# DIO_Isolation_Sheet.net
KiCad netlist of a schematic drawn in Altium Designer
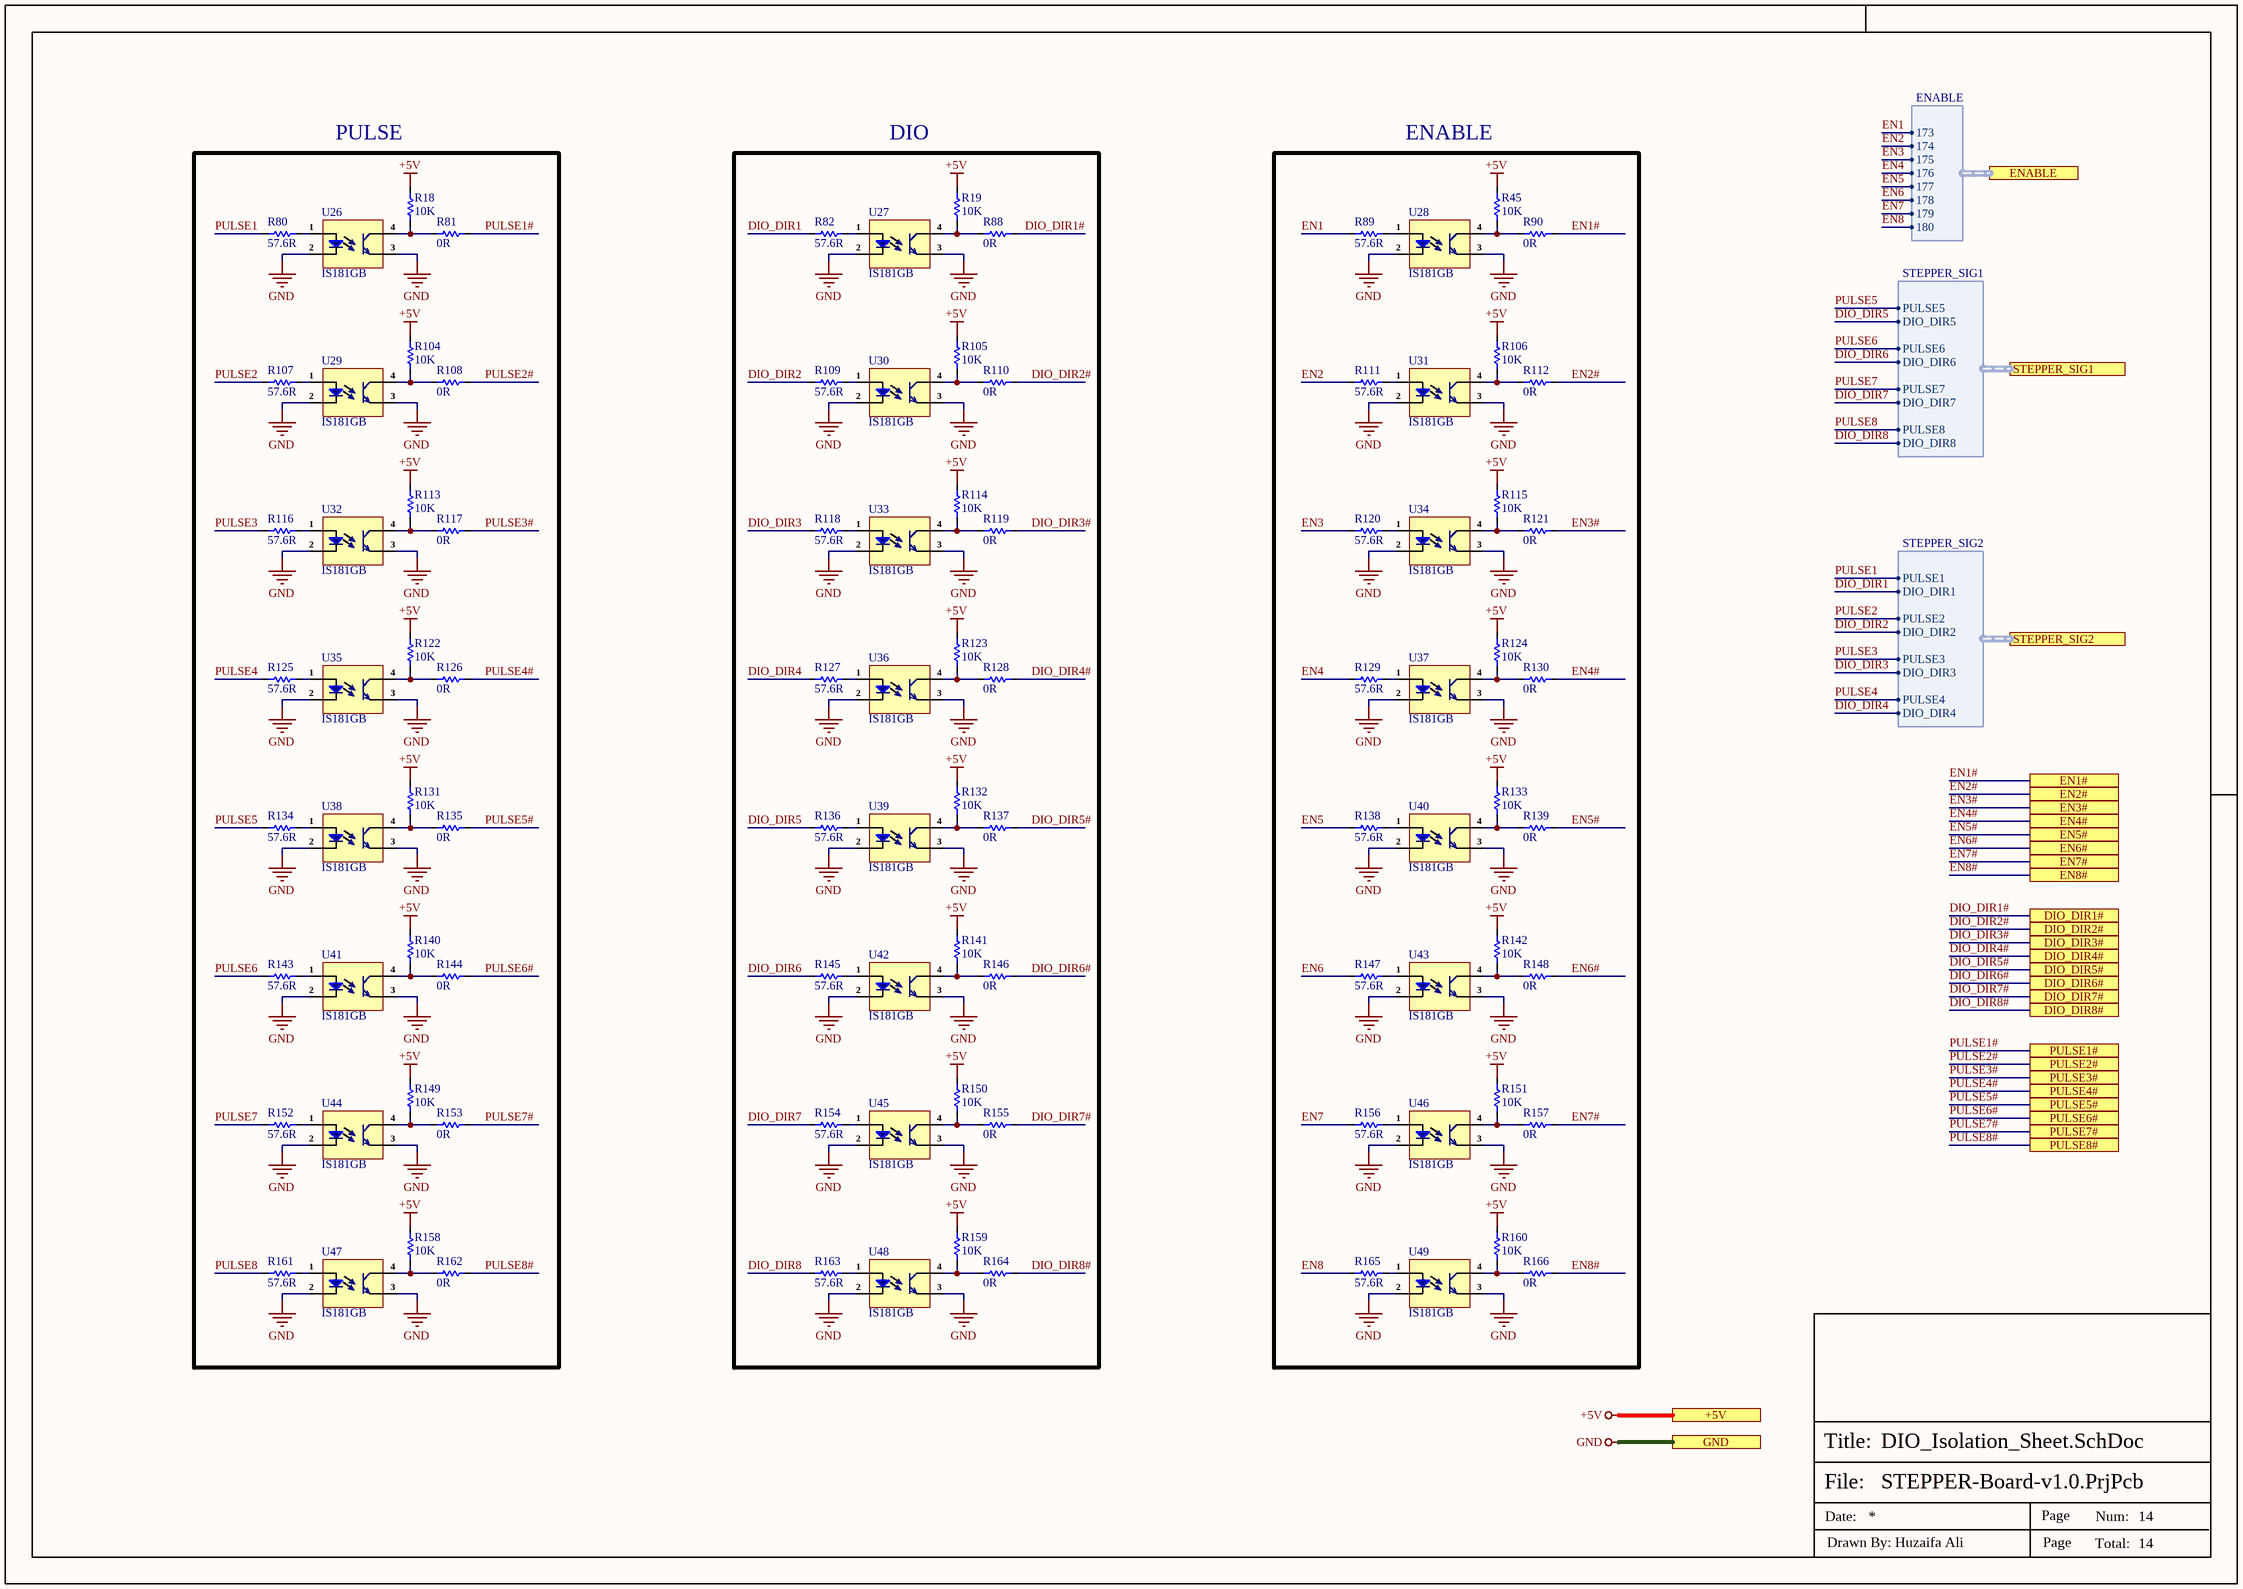
[diagram p0: DIO_Isolation_Sheet.SchDoc]

(export (version "E")
  (design (tool "Eeschema 10.0.6"))
  (components
    (comp (ref "R18")
      (value "10K")
      (footprint "Res-0402")
      (description "RES 10K OHM 1% 1/16W 0402")
      (fields
        (field (name "MANUFACTURER") "Yageo")
        (field (name "MANUFACTURER PART NUMBER") "RC0402FR-0710KL")
      )
      (libsource (lib "eSpark Libraries") (part "RC0402FR-0710KL"))
    )
    (comp (ref "R19")
      (value "10K")
      (footprint "Res-0402")
      (description "RES 10K OHM 1% 1/16W 0402")
      (fields
        (field (name "MANUFACTURER") "Yageo")
        (field (name "MANUFACTURER PART NUMBER") "RC0402FR-0710KL")
      )
      (libsource (lib "eSpark Libraries") (part "RC0402FR-0710KL"))
    )
    (comp (ref "R45")
      (value "10K")
      (footprint "Res-0402")
      (description "RES 10K OHM 1% 1/16W 0402")
      (fields
        (field (name "MANUFACTURER") "Yageo")
        (field (name "MANUFACTURER PART NUMBER") "RC0402FR-0710KL")
      )
      (libsource (lib "eSpark Libraries") (part "RC0402FR-0710KL"))
    )
    (comp (ref "R80")
      (value "57.6R")
      (footprint "Res-0402")
      (description "RES SMD 57.6 OHM 1% 1/10W 0402")
      (fields
        (field (name "MANUFACTURER") "Panasonic")
        (field (name "MANUFACTURER PART NUMBER") "ERJ-2RKF57R6X")
      )
      (libsource (lib "eSpark Libraries") (part "ERJ-2RKF57R6X"))
    )
    (comp (ref "R81")
      (value "0R")
      (footprint "Res-0402")
      (description "RES 0 OHM JUMPER 1/16W 0402")
      (fields
        (field (name "MANUFACTURER") "Yageo")
        (field (name "MANUFACTURER PART NUMBER") "RC0402FR-070RL")
      )
      (libsource (lib "eSpark Libraries") (part "RC0402FR-070RL"))
    )
    (comp (ref "R82")
      (value "57.6R")
      (footprint "Res-0402")
      (description "RES SMD 57.6 OHM 1% 1/10W 0402")
      (fields
        (field (name "MANUFACTURER") "Panasonic")
        (field (name "MANUFACTURER PART NUMBER") "ERJ-2RKF57R6X")
      )
      (libsource (lib "eSpark Libraries") (part "ERJ-2RKF57R6X"))
    )
    (comp (ref "R88")
      (value "0R")
      (footprint "Res-0402")
      (description "RES 0 OHM JUMPER 1/16W 0402")
      (fields
        (field (name "MANUFACTURER") "Yageo")
        (field (name "MANUFACTURER PART NUMBER") "RC0402FR-070RL")
      )
      (libsource (lib "eSpark Libraries") (part "RC0402FR-070RL"))
    )
    (comp (ref "R89")
      (value "57.6R")
      (footprint "Res-0402")
      (description "RES SMD 57.6 OHM 1% 1/10W 0402")
      (fields
        (field (name "MANUFACTURER") "Panasonic")
        (field (name "MANUFACTURER PART NUMBER") "ERJ-2RKF57R6X")
      )
      (libsource (lib "eSpark Libraries") (part "ERJ-2RKF57R6X"))
    )
    (comp (ref "R90")
      (value "0R")
      (footprint "Res-0402")
      (description "RES 0 OHM JUMPER 1/16W 0402")
      (fields
        (field (name "MANUFACTURER") "Yageo")
        (field (name "MANUFACTURER PART NUMBER") "RC0402FR-070RL")
      )
      (libsource (lib "eSpark Libraries") (part "RC0402FR-070RL"))
    )
    (comp (ref "R104")
      (value "10K")
      (footprint "Res-0402")
      (description "RES 10K OHM 1% 1/16W 0402")
      (fields
        (field (name "MANUFACTURER") "Yageo")
        (field (name "MANUFACTURER PART NUMBER") "RC0402FR-0710KL")
      )
      (libsource (lib "eSpark Libraries") (part "RC0402FR-0710KL"))
    )
    (comp (ref "R105")
      (value "10K")
      (footprint "Res-0402")
      (description "RES 10K OHM 1% 1/16W 0402")
      (fields
        (field (name "MANUFACTURER") "Yageo")
        (field (name "MANUFACTURER PART NUMBER") "RC0402FR-0710KL")
      )
      (libsource (lib "eSpark Libraries") (part "RC0402FR-0710KL"))
    )
    (comp (ref "R106")
      (value "10K")
      (footprint "Res-0402")
      (description "RES 10K OHM 1% 1/16W 0402")
      (fields
        (field (name "MANUFACTURER") "Yageo")
        (field (name "MANUFACTURER PART NUMBER") "RC0402FR-0710KL")
      )
      (libsource (lib "eSpark Libraries") (part "RC0402FR-0710KL"))
    )
    (comp (ref "R107")
      (value "57.6R")
      (footprint "Res-0402")
      (description "RES SMD 57.6 OHM 1% 1/10W 0402")
      (fields
        (field (name "MANUFACTURER") "Panasonic")
        (field (name "MANUFACTURER PART NUMBER") "ERJ-2RKF57R6X")
      )
      (libsource (lib "eSpark Libraries") (part "ERJ-2RKF57R6X"))
    )
    (comp (ref "R108")
      (value "0R")
      (footprint "Res-0402")
      (description "RES 0 OHM JUMPER 1/16W 0402")
      (fields
        (field (name "MANUFACTURER") "Yageo")
        (field (name "MANUFACTURER PART NUMBER") "RC0402FR-070RL")
      )
      (libsource (lib "eSpark Libraries") (part "RC0402FR-070RL"))
    )
    (comp (ref "R109")
      (value "57.6R")
      (footprint "Res-0402")
      (description "RES SMD 57.6 OHM 1% 1/10W 0402")
      (fields
        (field (name "MANUFACTURER") "Panasonic")
        (field (name "MANUFACTURER PART NUMBER") "ERJ-2RKF57R6X")
      )
      (libsource (lib "eSpark Libraries") (part "ERJ-2RKF57R6X"))
    )
    (comp (ref "R110")
      (value "0R")
      (footprint "Res-0402")
      (description "RES 0 OHM JUMPER 1/16W 0402")
      (fields
        (field (name "MANUFACTURER") "Yageo")
        (field (name "MANUFACTURER PART NUMBER") "RC0402FR-070RL")
      )
      (libsource (lib "eSpark Libraries") (part "RC0402FR-070RL"))
    )
    (comp (ref "R111")
      (value "57.6R")
      (footprint "Res-0402")
      (description "RES SMD 57.6 OHM 1% 1/10W 0402")
      (fields
        (field (name "MANUFACTURER") "Panasonic")
        (field (name "MANUFACTURER PART NUMBER") "ERJ-2RKF57R6X")
      )
      (libsource (lib "eSpark Libraries") (part "ERJ-2RKF57R6X"))
    )
    (comp (ref "R112")
      (value "0R")
      (footprint "Res-0402")
      (description "RES 0 OHM JUMPER 1/16W 0402")
      (fields
        (field (name "MANUFACTURER") "Yageo")
        (field (name "MANUFACTURER PART NUMBER") "RC0402FR-070RL")
      )
      (libsource (lib "eSpark Libraries") (part "RC0402FR-070RL"))
    )
    (comp (ref "R113")
      (value "10K")
      (footprint "Res-0402")
      (description "RES 10K OHM 1% 1/16W 0402")
      (fields
        (field (name "MANUFACTURER") "Yageo")
        (field (name "MANUFACTURER PART NUMBER") "RC0402FR-0710KL")
      )
      (libsource (lib "eSpark Libraries") (part "RC0402FR-0710KL"))
    )
    (comp (ref "R114")
      (value "10K")
      (footprint "Res-0402")
      (description "RES 10K OHM 1% 1/16W 0402")
      (fields
        (field (name "MANUFACTURER") "Yageo")
        (field (name "MANUFACTURER PART NUMBER") "RC0402FR-0710KL")
      )
      (libsource (lib "eSpark Libraries") (part "RC0402FR-0710KL"))
    )
    (comp (ref "R115")
      (value "10K")
      (footprint "Res-0402")
      (description "RES 10K OHM 1% 1/16W 0402")
      (fields
        (field (name "MANUFACTURER") "Yageo")
        (field (name "MANUFACTURER PART NUMBER") "RC0402FR-0710KL")
      )
      (libsource (lib "eSpark Libraries") (part "RC0402FR-0710KL"))
    )
    (comp (ref "R116")
      (value "57.6R")
      (footprint "Res-0402")
      (description "RES SMD 57.6 OHM 1% 1/10W 0402")
      (fields
        (field (name "MANUFACTURER") "Panasonic")
        (field (name "MANUFACTURER PART NUMBER") "ERJ-2RKF57R6X")
      )
      (libsource (lib "eSpark Libraries") (part "ERJ-2RKF57R6X"))
    )
    (comp (ref "R117")
      (value "0R")
      (footprint "Res-0402")
      (description "RES 0 OHM JUMPER 1/16W 0402")
      (fields
        (field (name "MANUFACTURER") "Yageo")
        (field (name "MANUFACTURER PART NUMBER") "RC0402FR-070RL")
      )
      (libsource (lib "eSpark Libraries") (part "RC0402FR-070RL"))
    )
    (comp (ref "R118")
      (value "57.6R")
      (footprint "Res-0402")
      (description "RES SMD 57.6 OHM 1% 1/10W 0402")
      (fields
        (field (name "MANUFACTURER") "Panasonic")
        (field (name "MANUFACTURER PART NUMBER") "ERJ-2RKF57R6X")
      )
      (libsource (lib "eSpark Libraries") (part "ERJ-2RKF57R6X"))
    )
    (comp (ref "R119")
      (value "0R")
      (footprint "Res-0402")
      (description "RES 0 OHM JUMPER 1/16W 0402")
      (fields
        (field (name "MANUFACTURER") "Yageo")
        (field (name "MANUFACTURER PART NUMBER") "RC0402FR-070RL")
      )
      (libsource (lib "eSpark Libraries") (part "RC0402FR-070RL"))
    )
    (comp (ref "R120")
      (value "57.6R")
      (footprint "Res-0402")
      (description "RES SMD 57.6 OHM 1% 1/10W 0402")
      (fields
        (field (name "MANUFACTURER") "Panasonic")
        (field (name "MANUFACTURER PART NUMBER") "ERJ-2RKF57R6X")
      )
      (libsource (lib "eSpark Libraries") (part "ERJ-2RKF57R6X"))
    )
    (comp (ref "R121")
      (value "0R")
      (footprint "Res-0402")
      (description "RES 0 OHM JUMPER 1/16W 0402")
      (fields
        (field (name "MANUFACTURER") "Yageo")
        (field (name "MANUFACTURER PART NUMBER") "RC0402FR-070RL")
      )
      (libsource (lib "eSpark Libraries") (part "RC0402FR-070RL"))
    )
    (comp (ref "R122")
      (value "10K")
      (footprint "Res-0402")
      (description "RES 10K OHM 1% 1/16W 0402")
      (fields
        (field (name "MANUFACTURER") "Yageo")
        (field (name "MANUFACTURER PART NUMBER") "RC0402FR-0710KL")
      )
      (libsource (lib "eSpark Libraries") (part "RC0402FR-0710KL"))
    )
    (comp (ref "R123")
      (value "10K")
      (footprint "Res-0402")
      (description "RES 10K OHM 1% 1/16W 0402")
      (fields
        (field (name "MANUFACTURER") "Yageo")
        (field (name "MANUFACTURER PART NUMBER") "RC0402FR-0710KL")
      )
      (libsource (lib "eSpark Libraries") (part "RC0402FR-0710KL"))
    )
    (comp (ref "R124")
      (value "10K")
      (footprint "Res-0402")
      (description "RES 10K OHM 1% 1/16W 0402")
      (fields
        (field (name "MANUFACTURER") "Yageo")
        (field (name "MANUFACTURER PART NUMBER") "RC0402FR-0710KL")
      )
      (libsource (lib "eSpark Libraries") (part "RC0402FR-0710KL"))
    )
    (comp (ref "R125")
      (value "57.6R")
      (footprint "Res-0402")
      (description "RES SMD 57.6 OHM 1% 1/10W 0402")
      (fields
        (field (name "MANUFACTURER") "Panasonic")
        (field (name "MANUFACTURER PART NUMBER") "ERJ-2RKF57R6X")
      )
      (libsource (lib "eSpark Libraries") (part "ERJ-2RKF57R6X"))
    )
    (comp (ref "R126")
      (value "0R")
      (footprint "Res-0402")
      (description "RES 0 OHM JUMPER 1/16W 0402")
      (fields
        (field (name "MANUFACTURER") "Yageo")
        (field (name "MANUFACTURER PART NUMBER") "RC0402FR-070RL")
      )
      (libsource (lib "eSpark Libraries") (part "RC0402FR-070RL"))
    )
    (comp (ref "R127")
      (value "57.6R")
      (footprint "Res-0402")
      (description "RES SMD 57.6 OHM 1% 1/10W 0402")
      (fields
        (field (name "MANUFACTURER") "Panasonic")
        (field (name "MANUFACTURER PART NUMBER") "ERJ-2RKF57R6X")
      )
      (libsource (lib "eSpark Libraries") (part "ERJ-2RKF57R6X"))
    )
    (comp (ref "R128")
      (value "0R")
      (footprint "Res-0402")
      (description "RES 0 OHM JUMPER 1/16W 0402")
      (fields
        (field (name "MANUFACTURER") "Yageo")
        (field (name "MANUFACTURER PART NUMBER") "RC0402FR-070RL")
      )
      (libsource (lib "eSpark Libraries") (part "RC0402FR-070RL"))
    )
    (comp (ref "R129")
      (value "57.6R")
      (footprint "Res-0402")
      (description "RES SMD 57.6 OHM 1% 1/10W 0402")
      (fields
        (field (name "MANUFACTURER") "Panasonic")
        (field (name "MANUFACTURER PART NUMBER") "ERJ-2RKF57R6X")
      )
      (libsource (lib "eSpark Libraries") (part "ERJ-2RKF57R6X"))
    )
    (comp (ref "R130")
      (value "0R")
      (footprint "Res-0402")
      (description "RES 0 OHM JUMPER 1/16W 0402")
      (fields
        (field (name "MANUFACTURER") "Yageo")
        (field (name "MANUFACTURER PART NUMBER") "RC0402FR-070RL")
      )
      (libsource (lib "eSpark Libraries") (part "RC0402FR-070RL"))
    )
    (comp (ref "R131")
      (value "10K")
      (footprint "Res-0402")
      (description "RES 10K OHM 1% 1/16W 0402")
      (fields
        (field (name "MANUFACTURER") "Yageo")
        (field (name "MANUFACTURER PART NUMBER") "RC0402FR-0710KL")
      )
      (libsource (lib "eSpark Libraries") (part "RC0402FR-0710KL"))
    )
    (comp (ref "R132")
      (value "10K")
      (footprint "Res-0402")
      (description "RES 10K OHM 1% 1/16W 0402")
      (fields
        (field (name "MANUFACTURER") "Yageo")
        (field (name "MANUFACTURER PART NUMBER") "RC0402FR-0710KL")
      )
      (libsource (lib "eSpark Libraries") (part "RC0402FR-0710KL"))
    )
    (comp (ref "R133")
      (value "10K")
      (footprint "Res-0402")
      (description "RES 10K OHM 1% 1/16W 0402")
      (fields
        (field (name "MANUFACTURER") "Yageo")
        (field (name "MANUFACTURER PART NUMBER") "RC0402FR-0710KL")
      )
      (libsource (lib "eSpark Libraries") (part "RC0402FR-0710KL"))
    )
    (comp (ref "R134")
      (value "57.6R")
      (footprint "Res-0402")
      (description "RES SMD 57.6 OHM 1% 1/10W 0402")
      (fields
        (field (name "MANUFACTURER") "Panasonic")
        (field (name "MANUFACTURER PART NUMBER") "ERJ-2RKF57R6X")
      )
      (libsource (lib "eSpark Libraries") (part "ERJ-2RKF57R6X"))
    )
    (comp (ref "R135")
      (value "0R")
      (footprint "Res-0402")
      (description "RES 0 OHM JUMPER 1/16W 0402")
      (fields
        (field (name "MANUFACTURER") "Yageo")
        (field (name "MANUFACTURER PART NUMBER") "RC0402FR-070RL")
      )
      (libsource (lib "eSpark Libraries") (part "RC0402FR-070RL"))
    )
    (comp (ref "R136")
      (value "57.6R")
      (footprint "Res-0402")
      (description "RES SMD 57.6 OHM 1% 1/10W 0402")
      (fields
        (field (name "MANUFACTURER") "Panasonic")
        (field (name "MANUFACTURER PART NUMBER") "ERJ-2RKF57R6X")
      )
      (libsource (lib "eSpark Libraries") (part "ERJ-2RKF57R6X"))
    )
    (comp (ref "R137")
      (value "0R")
      (footprint "Res-0402")
      (description "RES 0 OHM JUMPER 1/16W 0402")
      (fields
        (field (name "MANUFACTURER") "Yageo")
        (field (name "MANUFACTURER PART NUMBER") "RC0402FR-070RL")
      )
      (libsource (lib "eSpark Libraries") (part "RC0402FR-070RL"))
    )
    (comp (ref "R138")
      (value "57.6R")
      (footprint "Res-0402")
      (description "RES SMD 57.6 OHM 1% 1/10W 0402")
      (fields
        (field (name "MANUFACTURER") "Panasonic")
        (field (name "MANUFACTURER PART NUMBER") "ERJ-2RKF57R6X")
      )
      (libsource (lib "eSpark Libraries") (part "ERJ-2RKF57R6X"))
    )
    (comp (ref "R139")
      (value "0R")
      (footprint "Res-0402")
      (description "RES 0 OHM JUMPER 1/16W 0402")
      (fields
        (field (name "MANUFACTURER") "Yageo")
        (field (name "MANUFACTURER PART NUMBER") "RC0402FR-070RL")
      )
      (libsource (lib "eSpark Libraries") (part "RC0402FR-070RL"))
    )
    (comp (ref "R140")
      (value "10K")
      (footprint "Res-0402")
      (description "RES 10K OHM 1% 1/16W 0402")
      (fields
        (field (name "MANUFACTURER") "Yageo")
        (field (name "MANUFACTURER PART NUMBER") "RC0402FR-0710KL")
      )
      (libsource (lib "eSpark Libraries") (part "RC0402FR-0710KL"))
    )
    (comp (ref "R141")
      (value "10K")
      (footprint "Res-0402")
      (description "RES 10K OHM 1% 1/16W 0402")
      (fields
        (field (name "MANUFACTURER") "Yageo")
        (field (name "MANUFACTURER PART NUMBER") "RC0402FR-0710KL")
      )
      (libsource (lib "eSpark Libraries") (part "RC0402FR-0710KL"))
    )
    (comp (ref "R142")
      (value "10K")
      (footprint "Res-0402")
      (description "RES 10K OHM 1% 1/16W 0402")
      (fields
        (field (name "MANUFACTURER") "Yageo")
        (field (name "MANUFACTURER PART NUMBER") "RC0402FR-0710KL")
      )
      (libsource (lib "eSpark Libraries") (part "RC0402FR-0710KL"))
    )
    (comp (ref "R143")
      (value "57.6R")
      (footprint "Res-0402")
      (description "RES SMD 57.6 OHM 1% 1/10W 0402")
      (fields
        (field (name "MANUFACTURER") "Panasonic")
        (field (name "MANUFACTURER PART NUMBER") "ERJ-2RKF57R6X")
      )
      (libsource (lib "eSpark Libraries") (part "ERJ-2RKF57R6X"))
    )
    (comp (ref "R144")
      (value "0R")
      (footprint "Res-0402")
      (description "RES 0 OHM JUMPER 1/16W 0402")
      (fields
        (field (name "MANUFACTURER") "Yageo")
        (field (name "MANUFACTURER PART NUMBER") "RC0402FR-070RL")
      )
      (libsource (lib "eSpark Libraries") (part "RC0402FR-070RL"))
    )
    (comp (ref "R145")
      (value "57.6R")
      (footprint "Res-0402")
      (description "RES SMD 57.6 OHM 1% 1/10W 0402")
      (fields
        (field (name "MANUFACTURER") "Panasonic")
        (field (name "MANUFACTURER PART NUMBER") "ERJ-2RKF57R6X")
      )
      (libsource (lib "eSpark Libraries") (part "ERJ-2RKF57R6X"))
    )
    (comp (ref "R146")
      (value "0R")
      (footprint "Res-0402")
      (description "RES 0 OHM JUMPER 1/16W 0402")
      (fields
        (field (name "MANUFACTURER") "Yageo")
        (field (name "MANUFACTURER PART NUMBER") "RC0402FR-070RL")
      )
      (libsource (lib "eSpark Libraries") (part "RC0402FR-070RL"))
    )
    (comp (ref "R147")
      (value "57.6R")
      (footprint "Res-0402")
      (description "RES SMD 57.6 OHM 1% 1/10W 0402")
      (fields
        (field (name "MANUFACTURER") "Panasonic")
        (field (name "MANUFACTURER PART NUMBER") "ERJ-2RKF57R6X")
      )
      (libsource (lib "eSpark Libraries") (part "ERJ-2RKF57R6X"))
    )
    (comp (ref "R148")
      (value "0R")
      (footprint "Res-0402")
      (description "RES 0 OHM JUMPER 1/16W 0402")
      (fields
        (field (name "MANUFACTURER") "Yageo")
        (field (name "MANUFACTURER PART NUMBER") "RC0402FR-070RL")
      )
      (libsource (lib "eSpark Libraries") (part "RC0402FR-070RL"))
    )
    (comp (ref "R149")
      (value "10K")
      (footprint "Res-0402")
      (description "RES 10K OHM 1% 1/16W 0402")
      (fields
        (field (name "MANUFACTURER") "Yageo")
        (field (name "MANUFACTURER PART NUMBER") "RC0402FR-0710KL")
      )
      (libsource (lib "eSpark Libraries") (part "RC0402FR-0710KL"))
    )
    (comp (ref "R150")
      (value "10K")
      (footprint "Res-0402")
      (description "RES 10K OHM 1% 1/16W 0402")
      (fields
        (field (name "MANUFACTURER") "Yageo")
        (field (name "MANUFACTURER PART NUMBER") "RC0402FR-0710KL")
      )
      (libsource (lib "eSpark Libraries") (part "RC0402FR-0710KL"))
    )
    (comp (ref "R151")
      (value "10K")
      (footprint "Res-0402")
      (description "RES 10K OHM 1% 1/16W 0402")
      (fields
        (field (name "MANUFACTURER") "Yageo")
        (field (name "MANUFACTURER PART NUMBER") "RC0402FR-0710KL")
      )
      (libsource (lib "eSpark Libraries") (part "RC0402FR-0710KL"))
    )
    (comp (ref "R152")
      (value "57.6R")
      (footprint "Res-0402")
      (description "RES SMD 57.6 OHM 1% 1/10W 0402")
      (fields
        (field (name "MANUFACTURER") "Panasonic")
        (field (name "MANUFACTURER PART NUMBER") "ERJ-2RKF57R6X")
      )
      (libsource (lib "eSpark Libraries") (part "ERJ-2RKF57R6X"))
    )
    (comp (ref "R153")
      (value "0R")
      (footprint "Res-0402")
      (description "RES 0 OHM JUMPER 1/16W 0402")
      (fields
        (field (name "MANUFACTURER") "Yageo")
        (field (name "MANUFACTURER PART NUMBER") "RC0402FR-070RL")
      )
      (libsource (lib "eSpark Libraries") (part "RC0402FR-070RL"))
    )
    (comp (ref "R154")
      (value "57.6R")
      (footprint "Res-0402")
      (description "RES SMD 57.6 OHM 1% 1/10W 0402")
      (fields
        (field (name "MANUFACTURER") "Panasonic")
        (field (name "MANUFACTURER PART NUMBER") "ERJ-2RKF57R6X")
      )
      (libsource (lib "eSpark Libraries") (part "ERJ-2RKF57R6X"))
    )
    (comp (ref "R155")
      (value "0R")
      (footprint "Res-0402")
      (description "RES 0 OHM JUMPER 1/16W 0402")
      (fields
        (field (name "MANUFACTURER") "Yageo")
        (field (name "MANUFACTURER PART NUMBER") "RC0402FR-070RL")
      )
      (libsource (lib "eSpark Libraries") (part "RC0402FR-070RL"))
    )
    (comp (ref "R156")
      (value "57.6R")
      (footprint "Res-0402")
      (description "RES SMD 57.6 OHM 1% 1/10W 0402")
      (fields
        (field (name "MANUFACTURER") "Panasonic")
        (field (name "MANUFACTURER PART NUMBER") "ERJ-2RKF57R6X")
      )
      (libsource (lib "eSpark Libraries") (part "ERJ-2RKF57R6X"))
    )
    (comp (ref "R157")
      (value "0R")
      (footprint "Res-0402")
      (description "RES 0 OHM JUMPER 1/16W 0402")
      (fields
        (field (name "MANUFACTURER") "Yageo")
        (field (name "MANUFACTURER PART NUMBER") "RC0402FR-070RL")
      )
      (libsource (lib "eSpark Libraries") (part "RC0402FR-070RL"))
    )
    (comp (ref "R158")
      (value "10K")
      (footprint "Res-0402")
      (description "RES 10K OHM 1% 1/16W 0402")
      (fields
        (field (name "MANUFACTURER") "Yageo")
        (field (name "MANUFACTURER PART NUMBER") "RC0402FR-0710KL")
      )
      (libsource (lib "eSpark Libraries") (part "RC0402FR-0710KL"))
    )
    (comp (ref "R159")
      (value "10K")
      (footprint "Res-0402")
      (description "RES 10K OHM 1% 1/16W 0402")
      (fields
        (field (name "MANUFACTURER") "Yageo")
        (field (name "MANUFACTURER PART NUMBER") "RC0402FR-0710KL")
      )
      (libsource (lib "eSpark Libraries") (part "RC0402FR-0710KL"))
    )
    (comp (ref "R160")
      (value "10K")
      (footprint "Res-0402")
      (description "RES 10K OHM 1% 1/16W 0402")
      (fields
        (field (name "MANUFACTURER") "Yageo")
        (field (name "MANUFACTURER PART NUMBER") "RC0402FR-0710KL")
      )
      (libsource (lib "eSpark Libraries") (part "RC0402FR-0710KL"))
    )
    (comp (ref "R161")
      (value "57.6R")
      (footprint "Res-0402")
      (description "RES SMD 57.6 OHM 1% 1/10W 0402")
      (fields
        (field (name "MANUFACTURER") "Panasonic")
        (field (name "MANUFACTURER PART NUMBER") "ERJ-2RKF57R6X")
      )
      (libsource (lib "eSpark Libraries") (part "ERJ-2RKF57R6X"))
    )
    (comp (ref "R162")
      (value "0R")
      (footprint "Res-0402")
      (description "RES 0 OHM JUMPER 1/16W 0402")
      (fields
        (field (name "MANUFACTURER") "Yageo")
        (field (name "MANUFACTURER PART NUMBER") "RC0402FR-070RL")
      )
      (libsource (lib "eSpark Libraries") (part "RC0402FR-070RL"))
    )
    (comp (ref "R163")
      (value "57.6R")
      (footprint "Res-0402")
      (description "RES SMD 57.6 OHM 1% 1/10W 0402")
      (fields
        (field (name "MANUFACTURER") "Panasonic")
        (field (name "MANUFACTURER PART NUMBER") "ERJ-2RKF57R6X")
      )
      (libsource (lib "eSpark Libraries") (part "ERJ-2RKF57R6X"))
    )
    (comp (ref "R164")
      (value "0R")
      (footprint "Res-0402")
      (description "RES 0 OHM JUMPER 1/16W 0402")
      (fields
        (field (name "MANUFACTURER") "Yageo")
        (field (name "MANUFACTURER PART NUMBER") "RC0402FR-070RL")
      )
      (libsource (lib "eSpark Libraries") (part "RC0402FR-070RL"))
    )
    (comp (ref "R165")
      (value "57.6R")
      (footprint "Res-0402")
      (description "RES SMD 57.6 OHM 1% 1/10W 0402")
      (fields
        (field (name "MANUFACTURER") "Panasonic")
        (field (name "MANUFACTURER PART NUMBER") "ERJ-2RKF57R6X")
      )
      (libsource (lib "eSpark Libraries") (part "ERJ-2RKF57R6X"))
    )
    (comp (ref "R166")
      (value "0R")
      (footprint "Res-0402")
      (description "RES 0 OHM JUMPER 1/16W 0402")
      (fields
        (field (name "MANUFACTURER") "Yageo")
        (field (name "MANUFACTURER PART NUMBER") "RC0402FR-070RL")
      )
      (libsource (lib "eSpark Libraries") (part "RC0402FR-070RL"))
    )
    (comp (ref "U26")
      (value "IS181GB")
      (footprint "SOP-4_2.54")
      (description "Optoisolator Transistor Output 3750Vrms 1 Channel")
      (fields (field (name "MANUFACTURER") "Isocom") (field (name "LCSC PART NUMBER") "C84196"))
      (libsource (lib "eSpark Libraries") (part "IS181GB"))
    )
    (comp (ref "U27")
      (value "IS181GB")
      (footprint "SOP-4_2.54")
      (description "Optoisolator Transistor Output 3750Vrms 1 Channel")
      (fields (field (name "MANUFACTURER") "Isocom") (field (name "LCSC PART NUMBER") "C84196"))
      (libsource (lib "eSpark Libraries") (part "IS181GB"))
    )
    (comp (ref "U28")
      (value "IS181GB")
      (footprint "SOP-4_2.54")
      (description "Optoisolator Transistor Output 3750Vrms 1 Channel")
      (fields (field (name "MANUFACTURER") "Isocom") (field (name "LCSC PART NUMBER") "C84196"))
      (libsource (lib "eSpark Libraries") (part "IS181GB"))
    )
    (comp (ref "U29")
      (value "IS181GB")
      (footprint "SOP-4_2.54")
      (description "Optoisolator Transistor Output 3750Vrms 1 Channel")
      (fields (field (name "MANUFACTURER") "Isocom") (field (name "LCSC PART NUMBER") "C84196"))
      (libsource (lib "eSpark Libraries") (part "IS181GB"))
    )
    (comp (ref "U30")
      (value "IS181GB")
      (footprint "SOP-4_2.54")
      (description "Optoisolator Transistor Output 3750Vrms 1 Channel")
      (fields (field (name "MANUFACTURER") "Isocom") (field (name "LCSC PART NUMBER") "C84196"))
      (libsource (lib "eSpark Libraries") (part "IS181GB"))
    )
    (comp (ref "U31")
      (value "IS181GB")
      (footprint "SOP-4_2.54")
      (description "Optoisolator Transistor Output 3750Vrms 1 Channel")
      (fields (field (name "MANUFACTURER") "Isocom") (field (name "LCSC PART NUMBER") "C84196"))
      (libsource (lib "eSpark Libraries") (part "IS181GB"))
    )
    (comp (ref "U32")
      (value "IS181GB")
      (footprint "SOP-4_2.54")
      (description "Optoisolator Transistor Output 3750Vrms 1 Channel")
      (fields (field (name "MANUFACTURER") "Isocom") (field (name "LCSC PART NUMBER") "C84196"))
      (libsource (lib "eSpark Libraries") (part "IS181GB"))
    )
    (comp (ref "U33")
      (value "IS181GB")
      (footprint "SOP-4_2.54")
      (description "Optoisolator Transistor Output 3750Vrms 1 Channel")
      (fields (field (name "MANUFACTURER") "Isocom") (field (name "LCSC PART NUMBER") "C84196"))
      (libsource (lib "eSpark Libraries") (part "IS181GB"))
    )
    (comp (ref "U34")
      (value "IS181GB")
      (footprint "SOP-4_2.54")
      (description "Optoisolator Transistor Output 3750Vrms 1 Channel")
      (fields (field (name "MANUFACTURER") "Isocom") (field (name "LCSC PART NUMBER") "C84196"))
      (libsource (lib "eSpark Libraries") (part "IS181GB"))
    )
    (comp (ref "U35")
      (value "IS181GB")
      (footprint "SOP-4_2.54")
      (description "Optoisolator Transistor Output 3750Vrms 1 Channel")
      (fields (field (name "MANUFACTURER") "Isocom") (field (name "LCSC PART NUMBER") "C84196"))
      (libsource (lib "eSpark Libraries") (part "IS181GB"))
    )
    (comp (ref "U36")
      (value "IS181GB")
      (footprint "SOP-4_2.54")
      (description "Optoisolator Transistor Output 3750Vrms 1 Channel")
      (fields (field (name "MANUFACTURER") "Isocom") (field (name "LCSC PART NUMBER") "C84196"))
      (libsource (lib "eSpark Libraries") (part "IS181GB"))
    )
    (comp (ref "U37")
      (value "IS181GB")
      (footprint "SOP-4_2.54")
      (description "Optoisolator Transistor Output 3750Vrms 1 Channel")
      (fields (field (name "MANUFACTURER") "Isocom") (field (name "LCSC PART NUMBER") "C84196"))
      (libsource (lib "eSpark Libraries") (part "IS181GB"))
    )
    (comp (ref "U38")
      (value "IS181GB")
      (footprint "SOP-4_2.54")
      (description "Optoisolator Transistor Output 3750Vrms 1 Channel")
      (fields (field (name "MANUFACTURER") "Isocom") (field (name "LCSC PART NUMBER") "C84196"))
      (libsource (lib "eSpark Libraries") (part "IS181GB"))
    )
    (comp (ref "U39")
      (value "IS181GB")
      (footprint "SOP-4_2.54")
      (description "Optoisolator Transistor Output 3750Vrms 1 Channel")
      (fields (field (name "MANUFACTURER") "Isocom") (field (name "LCSC PART NUMBER") "C84196"))
      (libsource (lib "eSpark Libraries") (part "IS181GB"))
    )
    (comp (ref "U40")
      (value "IS181GB")
      (footprint "SOP-4_2.54")
      (description "Optoisolator Transistor Output 3750Vrms 1 Channel")
      (fields (field (name "MANUFACTURER") "Isocom") (field (name "LCSC PART NUMBER") "C84196"))
      (libsource (lib "eSpark Libraries") (part "IS181GB"))
    )
    (comp (ref "U41")
      (value "IS181GB")
      (footprint "SOP-4_2.54")
      (description "Optoisolator Transistor Output 3750Vrms 1 Channel")
      (fields (field (name "MANUFACTURER") "Isocom") (field (name "LCSC PART NUMBER") "C84196"))
      (libsource (lib "eSpark Libraries") (part "IS181GB"))
    )
    (comp (ref "U42")
      (value "IS181GB")
      (footprint "SOP-4_2.54")
      (description "Optoisolator Transistor Output 3750Vrms 1 Channel")
      (fields (field (name "MANUFACTURER") "Isocom") (field (name "LCSC PART NUMBER") "C84196"))
      (libsource (lib "eSpark Libraries") (part "IS181GB"))
    )
    (comp (ref "U43")
      (value "IS181GB")
      (footprint "SOP-4_2.54")
      (description "Optoisolator Transistor Output 3750Vrms 1 Channel")
      (fields (field (name "MANUFACTURER") "Isocom") (field (name "LCSC PART NUMBER") "C84196"))
      (libsource (lib "eSpark Libraries") (part "IS181GB"))
    )
    (comp (ref "U44")
      (value "IS181GB")
      (footprint "SOP-4_2.54")
      (description "Optoisolator Transistor Output 3750Vrms 1 Channel")
      (fields (field (name "MANUFACTURER") "Isocom") (field (name "LCSC PART NUMBER") "C84196"))
      (libsource (lib "eSpark Libraries") (part "IS181GB"))
    )
    (comp (ref "U45")
      (value "IS181GB")
      (footprint "SOP-4_2.54")
      (description "Optoisolator Transistor Output 3750Vrms 1 Channel")
      (fields (field (name "MANUFACTURER") "Isocom") (field (name "LCSC PART NUMBER") "C84196"))
      (libsource (lib "eSpark Libraries") (part "IS181GB"))
    )
    (comp (ref "U46")
      (value "IS181GB")
      (footprint "SOP-4_2.54")
      (description "Optoisolator Transistor Output 3750Vrms 1 Channel")
      (fields (field (name "MANUFACTURER") "Isocom") (field (name "LCSC PART NUMBER") "C84196"))
      (libsource (lib "eSpark Libraries") (part "IS181GB"))
    )
    (comp (ref "U47")
      (value "IS181GB")
      (footprint "SOP-4_2.54")
      (description "Optoisolator Transistor Output 3750Vrms 1 Channel")
      (fields (field (name "MANUFACTURER") "Isocom") (field (name "LCSC PART NUMBER") "C84196"))
      (libsource (lib "eSpark Libraries") (part "IS181GB"))
    )
    (comp (ref "U48")
      (value "IS181GB")
      (footprint "SOP-4_2.54")
      (description "Optoisolator Transistor Output 3750Vrms 1 Channel")
      (fields (field (name "MANUFACTURER") "Isocom") (field (name "LCSC PART NUMBER") "C84196"))
      (libsource (lib "eSpark Libraries") (part "IS181GB"))
    )
    (comp (ref "U49")
      (value "IS181GB")
      (footprint "SOP-4_2.54")
      (description "Optoisolator Transistor Output 3750Vrms 1 Channel")
      (fields (field (name "MANUFACTURER") "Isocom") (field (name "LCSC PART NUMBER") "C84196"))
      (libsource (lib "eSpark Libraries") (part "IS181GB"))
    )
  )
  (nets
    (net (code "4") (name "+5V") (class "Default")
      (node (ref "R104") (pin "2") (pinfunction "2_2") (pintype "passive"))
      (node (ref "R105") (pin "2") (pinfunction "2_2") (pintype "passive"))
      (node (ref "R106") (pin "2") (pinfunction "2_2") (pintype "passive"))
      (node (ref "R113") (pin "2") (pinfunction "2_2") (pintype "passive"))
      (node (ref "R114") (pin "2") (pinfunction "2_2") (pintype "passive"))
      (node (ref "R115") (pin "2") (pinfunction "2_2") (pintype "passive"))
      (node (ref "R122") (pin "2") (pinfunction "2_2") (pintype "passive"))
      (node (ref "R123") (pin "2") (pinfunction "2_2") (pintype "passive"))
      (node (ref "R124") (pin "2") (pinfunction "2_2") (pintype "passive"))
      (node (ref "R131") (pin "2") (pinfunction "2_2") (pintype "passive"))
      (node (ref "R132") (pin "2") (pinfunction "2_2") (pintype "passive"))
      (node (ref "R133") (pin "2") (pinfunction "2_2") (pintype "passive"))
      (node (ref "R140") (pin "2") (pinfunction "2_2") (pintype "passive"))
      (node (ref "R141") (pin "2") (pinfunction "2_2") (pintype "passive"))
      (node (ref "R142") (pin "2") (pinfunction "2_2") (pintype "passive"))
      (node (ref "R149") (pin "2") (pinfunction "2_2") (pintype "passive"))
      (node (ref "R150") (pin "2") (pinfunction "2_2") (pintype "passive"))
      (node (ref "R151") (pin "2") (pinfunction "2_2") (pintype "passive"))
      (node (ref "R158") (pin "2") (pinfunction "2_2") (pintype "passive"))
      (node (ref "R159") (pin "2") (pinfunction "2_2") (pintype "passive"))
      (node (ref "R160") (pin "2") (pinfunction "2_2") (pintype "passive"))
      (node (ref "R18") (pin "2") (pinfunction "2_2") (pintype "passive"))
      (node (ref "R19") (pin "2") (pinfunction "2_2") (pintype "passive"))
      (node (ref "R45") (pin "2") (pinfunction "2_2") (pintype "passive"))
    )
    (net (code "5") (name "/DIO_DIR1") (class "Default")
      (node (ref "R82") (pin "1") (pinfunction "1_1") (pintype "passive"))
    )
    (net (code "6") (name "/DIO_DIR1#") (class "Default")
      (node (ref "R88") (pin "2") (pinfunction "2_2") (pintype "passive"))
    )
    (net (code "7") (name "/DIO_DIR2") (class "Default")
      (node (ref "R109") (pin "1") (pinfunction "1_1") (pintype "passive"))
    )
    (net (code "8") (name "/DIO_DIR2#") (class "Default")
      (node (ref "R110") (pin "2") (pinfunction "2_2") (pintype "passive"))
    )
    (net (code "9") (name "/DIO_DIR3") (class "Default")
      (node (ref "R118") (pin "1") (pinfunction "1_1") (pintype "passive"))
    )
    (net (code "10") (name "/DIO_DIR3#") (class "Default")
      (node (ref "R119") (pin "2") (pinfunction "2_2") (pintype "passive"))
    )
    (net (code "11") (name "/DIO_DIR4") (class "Default")
      (node (ref "R127") (pin "1") (pinfunction "1_1") (pintype "passive"))
    )
    (net (code "12") (name "/DIO_DIR4#") (class "Default")
      (node (ref "R128") (pin "2") (pinfunction "2_2") (pintype "passive"))
    )
    (net (code "13") (name "/DIO_DIR5") (class "Default")
      (node (ref "R136") (pin "1") (pinfunction "1_1") (pintype "passive"))
    )
    (net (code "14") (name "/DIO_DIR5#") (class "Default")
      (node (ref "R137") (pin "2") (pinfunction "2_2") (pintype "passive"))
    )
    (net (code "15") (name "/DIO_DIR6") (class "Default")
      (node (ref "R145") (pin "1") (pinfunction "1_1") (pintype "passive"))
    )
    (net (code "16") (name "/DIO_DIR6#") (class "Default")
      (node (ref "R146") (pin "2") (pinfunction "2_2") (pintype "passive"))
    )
    (net (code "17") (name "/DIO_DIR7") (class "Default")
      (node (ref "R154") (pin "1") (pinfunction "1_1") (pintype "passive"))
    )
    (net (code "18") (name "/DIO_DIR7#") (class "Default")
      (node (ref "R155") (pin "2") (pinfunction "2_2") (pintype "passive"))
    )
    (net (code "19") (name "/DIO_DIR8") (class "Default")
      (node (ref "R163") (pin "1") (pinfunction "1_1") (pintype "passive"))
    )
    (net (code "20") (name "/DIO_DIR8#") (class "Default")
      (node (ref "R164") (pin "2") (pinfunction "2_2") (pintype "passive"))
    )
    (net (code "21") (name "/EN1") (class "Default")
      (node (ref "R89") (pin "1") (pinfunction "1_1") (pintype "passive"))
    )
    (net (code "22") (name "/EN1#") (class "Default")
      (node (ref "R90") (pin "2") (pinfunction "2_2") (pintype "passive"))
    )
    (net (code "23") (name "/EN2") (class "Default")
      (node (ref "R111") (pin "1") (pinfunction "1_1") (pintype "passive"))
    )
    (net (code "24") (name "/EN2#") (class "Default")
      (node (ref "R112") (pin "2") (pinfunction "2_2") (pintype "passive"))
    )
    (net (code "25") (name "/EN3") (class "Default")
      (node (ref "R120") (pin "1") (pinfunction "1_1") (pintype "passive"))
    )
    (net (code "26") (name "/EN3#") (class "Default")
      (node (ref "R121") (pin "2") (pinfunction "2_2") (pintype "passive"))
    )
    (net (code "27") (name "/EN4") (class "Default")
      (node (ref "R129") (pin "1") (pinfunction "1_1") (pintype "passive"))
    )
    (net (code "28") (name "/EN4#") (class "Default")
      (node (ref "R130") (pin "2") (pinfunction "2_2") (pintype "passive"))
    )
    (net (code "29") (name "/EN5") (class "Default")
      (node (ref "R138") (pin "1") (pinfunction "1_1") (pintype "passive"))
    )
    (net (code "30") (name "/EN5#") (class "Default")
      (node (ref "R139") (pin "2") (pinfunction "2_2") (pintype "passive"))
    )
    (net (code "31") (name "/EN6") (class "Default")
      (node (ref "R147") (pin "1") (pinfunction "1_1") (pintype "passive"))
    )
    (net (code "32") (name "/EN6#") (class "Default")
      (node (ref "R148") (pin "2") (pinfunction "2_2") (pintype "passive"))
    )
    (net (code "33") (name "/EN7") (class "Default")
      (node (ref "R156") (pin "1") (pinfunction "1_1") (pintype "passive"))
    )
    (net (code "34") (name "/EN7#") (class "Default")
      (node (ref "R157") (pin "2") (pinfunction "2_2") (pintype "passive"))
    )
    (net (code "35") (name "/EN8") (class "Default")
      (node (ref "R165") (pin "1") (pinfunction "1_1") (pintype "passive"))
    )
    (net (code "36") (name "/EN8#") (class "Default")
      (node (ref "R166") (pin "2") (pinfunction "2_2") (pintype "passive"))
    )
    (net (code "37") (name "/PULSE1") (class "Default")
      (node (ref "R80") (pin "1") (pinfunction "1_1") (pintype "passive"))
    )
    (net (code "38") (name "/PULSE1#") (class "Default")
      (node (ref "R81") (pin "2") (pinfunction "2_2") (pintype "passive"))
    )
    (net (code "39") (name "/PULSE2") (class "Default")
      (node (ref "R107") (pin "1") (pinfunction "1_1") (pintype "passive"))
    )
    (net (code "40") (name "/PULSE2#") (class "Default")
      (node (ref "R108") (pin "2") (pinfunction "2_2") (pintype "passive"))
    )
    (net (code "41") (name "/PULSE3") (class "Default")
      (node (ref "R116") (pin "1") (pinfunction "1_1") (pintype "passive"))
    )
    (net (code "42") (name "/PULSE3#") (class "Default")
      (node (ref "R117") (pin "2") (pinfunction "2_2") (pintype "passive"))
    )
    (net (code "43") (name "/PULSE4") (class "Default")
      (node (ref "R125") (pin "1") (pinfunction "1_1") (pintype "passive"))
    )
    (net (code "44") (name "/PULSE4#") (class "Default")
      (node (ref "R126") (pin "2") (pinfunction "2_2") (pintype "passive"))
    )
    (net (code "45") (name "/PULSE5") (class "Default")
      (node (ref "R134") (pin "1") (pinfunction "1_1") (pintype "passive"))
    )
    (net (code "46") (name "/PULSE5#") (class "Default")
      (node (ref "R135") (pin "2") (pinfunction "2_2") (pintype "passive"))
    )
    (net (code "47") (name "/PULSE6") (class "Default")
      (node (ref "R143") (pin "1") (pinfunction "1_1") (pintype "passive"))
    )
    (net (code "48") (name "/PULSE6#") (class "Default")
      (node (ref "R144") (pin "2") (pinfunction "2_2") (pintype "passive"))
    )
    (net (code "49") (name "/PULSE7") (class "Default")
      (node (ref "R152") (pin "1") (pinfunction "1_1") (pintype "passive"))
    )
    (net (code "50") (name "/PULSE7#") (class "Default")
      (node (ref "R153") (pin "2") (pinfunction "2_2") (pintype "passive"))
    )
    (net (code "51") (name "/PULSE8") (class "Default")
      (node (ref "R161") (pin "1") (pinfunction "1_1") (pintype "passive"))
    )
    (net (code "52") (name "/PULSE8#") (class "Default")
      (node (ref "R162") (pin "2") (pinfunction "2_2") (pintype "passive"))
    )
    (net (code "56") (name "GND") (class "Default")
      (node (ref "U26") (pin "2") (pinfunction "Ca_2") (pintype "passive"))
      (node (ref "U26") (pin "3") (pinfunction "E_3") (pintype "passive"))
      (node (ref "U27") (pin "2") (pinfunction "Ca_2") (pintype "passive"))
      (node (ref "U27") (pin "3") (pinfunction "E_3") (pintype "passive"))
      (node (ref "U28") (pin "2") (pinfunction "Ca_2") (pintype "passive"))
      (node (ref "U28") (pin "3") (pinfunction "E_3") (pintype "passive"))
      (node (ref "U29") (pin "2") (pinfunction "Ca_2") (pintype "passive"))
      (node (ref "U29") (pin "3") (pinfunction "E_3") (pintype "passive"))
      (node (ref "U30") (pin "2") (pinfunction "Ca_2") (pintype "passive"))
      (node (ref "U30") (pin "3") (pinfunction "E_3") (pintype "passive"))
      (node (ref "U31") (pin "2") (pinfunction "Ca_2") (pintype "passive"))
      (node (ref "U31") (pin "3") (pinfunction "E_3") (pintype "passive"))
      (node (ref "U32") (pin "2") (pinfunction "Ca_2") (pintype "passive"))
      (node (ref "U32") (pin "3") (pinfunction "E_3") (pintype "passive"))
      (node (ref "U33") (pin "2") (pinfunction "Ca_2") (pintype "passive"))
      (node (ref "U33") (pin "3") (pinfunction "E_3") (pintype "passive"))
      (node (ref "U34") (pin "2") (pinfunction "Ca_2") (pintype "passive"))
      (node (ref "U34") (pin "3") (pinfunction "E_3") (pintype "passive"))
      (node (ref "U35") (pin "2") (pinfunction "Ca_2") (pintype "passive"))
      (node (ref "U35") (pin "3") (pinfunction "E_3") (pintype "passive"))
      (node (ref "U36") (pin "2") (pinfunction "Ca_2") (pintype "passive"))
      (node (ref "U36") (pin "3") (pinfunction "E_3") (pintype "passive"))
      (node (ref "U37") (pin "2") (pinfunction "Ca_2") (pintype "passive"))
      (node (ref "U37") (pin "3") (pinfunction "E_3") (pintype "passive"))
      (node (ref "U38") (pin "2") (pinfunction "Ca_2") (pintype "passive"))
      (node (ref "U38") (pin "3") (pinfunction "E_3") (pintype "passive"))
      (node (ref "U39") (pin "2") (pinfunction "Ca_2") (pintype "passive"))
      (node (ref "U39") (pin "3") (pinfunction "E_3") (pintype "passive"))
      (node (ref "U40") (pin "2") (pinfunction "Ca_2") (pintype "passive"))
      (node (ref "U40") (pin "3") (pinfunction "E_3") (pintype "passive"))
      (node (ref "U41") (pin "2") (pinfunction "Ca_2") (pintype "passive"))
      (node (ref "U41") (pin "3") (pinfunction "E_3") (pintype "passive"))
      (node (ref "U42") (pin "2") (pinfunction "Ca_2") (pintype "passive"))
      (node (ref "U42") (pin "3") (pinfunction "E_3") (pintype "passive"))
      (node (ref "U43") (pin "2") (pinfunction "Ca_2") (pintype "passive"))
      (node (ref "U43") (pin "3") (pinfunction "E_3") (pintype "passive"))
      (node (ref "U44") (pin "2") (pinfunction "Ca_2") (pintype "passive"))
      (node (ref "U44") (pin "3") (pinfunction "E_3") (pintype "passive"))
      (node (ref "U45") (pin "2") (pinfunction "Ca_2") (pintype "passive"))
      (node (ref "U45") (pin "3") (pinfunction "E_3") (pintype "passive"))
      (node (ref "U46") (pin "2") (pinfunction "Ca_2") (pintype "passive"))
      (node (ref "U46") (pin "3") (pinfunction "E_3") (pintype "passive"))
      (node (ref "U47") (pin "2") (pinfunction "Ca_2") (pintype "passive"))
      (node (ref "U47") (pin "3") (pinfunction "E_3") (pintype "passive"))
      (node (ref "U48") (pin "2") (pinfunction "Ca_2") (pintype "passive"))
      (node (ref "U48") (pin "3") (pinfunction "E_3") (pintype "passive"))
      (node (ref "U49") (pin "2") (pinfunction "Ca_2") (pintype "passive"))
      (node (ref "U49") (pin "3") (pinfunction "E_3") (pintype "passive"))
    )
    (net (code "57") (name "Net-(U26-An)") (class "Default")
      (node (ref "R80") (pin "2") (pinfunction "2_2") (pintype "passive"))
      (node (ref "U26") (pin "1") (pinfunction "An_1") (pintype "passive"))
    )
    (net (code "58") (name "Net-(U26-C)") (class "Default")
      (node (ref "R18") (pin "1") (pinfunction "1_1") (pintype "passive"))
      (node (ref "R81") (pin "1") (pinfunction "1_1") (pintype "passive"))
      (node (ref "U26") (pin "4") (pinfunction "C_4") (pintype "passive"))
    )
    (net (code "59") (name "Net-(U27-An)") (class "Default")
      (node (ref "R82") (pin "2") (pinfunction "2_2") (pintype "passive"))
      (node (ref "U27") (pin "1") (pinfunction "An_1") (pintype "passive"))
    )
    (net (code "60") (name "Net-(U27-C)") (class "Default")
      (node (ref "R19") (pin "1") (pinfunction "1_1") (pintype "passive"))
      (node (ref "R88") (pin "1") (pinfunction "1_1") (pintype "passive"))
      (node (ref "U27") (pin "4") (pinfunction "C_4") (pintype "passive"))
    )
    (net (code "61") (name "Net-(U28-An)") (class "Default")
      (node (ref "R89") (pin "2") (pinfunction "2_2") (pintype "passive"))
      (node (ref "U28") (pin "1") (pinfunction "An_1") (pintype "passive"))
    )
    (net (code "62") (name "Net-(U28-C)") (class "Default")
      (node (ref "R45") (pin "1") (pinfunction "1_1") (pintype "passive"))
      (node (ref "R90") (pin "1") (pinfunction "1_1") (pintype "passive"))
      (node (ref "U28") (pin "4") (pinfunction "C_4") (pintype "passive"))
    )
    (net (code "63") (name "Net-(U29-An)") (class "Default")
      (node (ref "R107") (pin "2") (pinfunction "2_2") (pintype "passive"))
      (node (ref "U29") (pin "1") (pinfunction "An_1") (pintype "passive"))
    )
    (net (code "64") (name "Net-(U29-C)") (class "Default")
      (node (ref "R104") (pin "1") (pinfunction "1_1") (pintype "passive"))
      (node (ref "R108") (pin "1") (pinfunction "1_1") (pintype "passive"))
      (node (ref "U29") (pin "4") (pinfunction "C_4") (pintype "passive"))
    )
    (net (code "65") (name "Net-(U30-An)") (class "Default")
      (node (ref "R109") (pin "2") (pinfunction "2_2") (pintype "passive"))
      (node (ref "U30") (pin "1") (pinfunction "An_1") (pintype "passive"))
    )
    (net (code "66") (name "Net-(U30-C)") (class "Default")
      (node (ref "R105") (pin "1") (pinfunction "1_1") (pintype "passive"))
      (node (ref "R110") (pin "1") (pinfunction "1_1") (pintype "passive"))
      (node (ref "U30") (pin "4") (pinfunction "C_4") (pintype "passive"))
    )
    (net (code "67") (name "Net-(U31-An)") (class "Default")
      (node (ref "R111") (pin "2") (pinfunction "2_2") (pintype "passive"))
      (node (ref "U31") (pin "1") (pinfunction "An_1") (pintype "passive"))
    )
    (net (code "68") (name "Net-(U31-C)") (class "Default")
      (node (ref "R106") (pin "1") (pinfunction "1_1") (pintype "passive"))
      (node (ref "R112") (pin "1") (pinfunction "1_1") (pintype "passive"))
      (node (ref "U31") (pin "4") (pinfunction "C_4") (pintype "passive"))
    )
    (net (code "69") (name "Net-(U32-An)") (class "Default")
      (node (ref "R116") (pin "2") (pinfunction "2_2") (pintype "passive"))
      (node (ref "U32") (pin "1") (pinfunction "An_1") (pintype "passive"))
    )
    (net (code "70") (name "Net-(U32-C)") (class "Default")
      (node (ref "R113") (pin "1") (pinfunction "1_1") (pintype "passive"))
      (node (ref "R117") (pin "1") (pinfunction "1_1") (pintype "passive"))
      (node (ref "U32") (pin "4") (pinfunction "C_4") (pintype "passive"))
    )
    (net (code "71") (name "Net-(U33-An)") (class "Default")
      (node (ref "R118") (pin "2") (pinfunction "2_2") (pintype "passive"))
      (node (ref "U33") (pin "1") (pinfunction "An_1") (pintype "passive"))
    )
    (net (code "72") (name "Net-(U33-C)") (class "Default")
      (node (ref "R114") (pin "1") (pinfunction "1_1") (pintype "passive"))
      (node (ref "R119") (pin "1") (pinfunction "1_1") (pintype "passive"))
      (node (ref "U33") (pin "4") (pinfunction "C_4") (pintype "passive"))
    )
    (net (code "73") (name "Net-(U34-An)") (class "Default")
      (node (ref "R120") (pin "2") (pinfunction "2_2") (pintype "passive"))
      (node (ref "U34") (pin "1") (pinfunction "An_1") (pintype "passive"))
    )
    (net (code "74") (name "Net-(U34-C)") (class "Default")
      (node (ref "R115") (pin "1") (pinfunction "1_1") (pintype "passive"))
      (node (ref "R121") (pin "1") (pinfunction "1_1") (pintype "passive"))
      (node (ref "U34") (pin "4") (pinfunction "C_4") (pintype "passive"))
    )
    (net (code "75") (name "Net-(U35-An)") (class "Default")
      (node (ref "R125") (pin "2") (pinfunction "2_2") (pintype "passive"))
      (node (ref "U35") (pin "1") (pinfunction "An_1") (pintype "passive"))
    )
    (net (code "76") (name "Net-(U35-C)") (class "Default")
      (node (ref "R122") (pin "1") (pinfunction "1_1") (pintype "passive"))
      (node (ref "R126") (pin "1") (pinfunction "1_1") (pintype "passive"))
      (node (ref "U35") (pin "4") (pinfunction "C_4") (pintype "passive"))
    )
    (net (code "77") (name "Net-(U36-An)") (class "Default")
      (node (ref "R127") (pin "2") (pinfunction "2_2") (pintype "passive"))
      (node (ref "U36") (pin "1") (pinfunction "An_1") (pintype "passive"))
    )
    (net (code "78") (name "Net-(U36-C)") (class "Default")
      (node (ref "R123") (pin "1") (pinfunction "1_1") (pintype "passive"))
      (node (ref "R128") (pin "1") (pinfunction "1_1") (pintype "passive"))
      (node (ref "U36") (pin "4") (pinfunction "C_4") (pintype "passive"))
    )
    (net (code "79") (name "Net-(U37-An)") (class "Default")
      (node (ref "R129") (pin "2") (pinfunction "2_2") (pintype "passive"))
      (node (ref "U37") (pin "1") (pinfunction "An_1") (pintype "passive"))
    )
    (net (code "80") (name "Net-(U37-C)") (class "Default")
      (node (ref "R124") (pin "1") (pinfunction "1_1") (pintype "passive"))
      (node (ref "R130") (pin "1") (pinfunction "1_1") (pintype "passive"))
      (node (ref "U37") (pin "4") (pinfunction "C_4") (pintype "passive"))
    )
    (net (code "81") (name "Net-(U38-An)") (class "Default")
      (node (ref "R134") (pin "2") (pinfunction "2_2") (pintype "passive"))
      (node (ref "U38") (pin "1") (pinfunction "An_1") (pintype "passive"))
    )
    (net (code "82") (name "Net-(U38-C)") (class "Default")
      (node (ref "R131") (pin "1") (pinfunction "1_1") (pintype "passive"))
      (node (ref "R135") (pin "1") (pinfunction "1_1") (pintype "passive"))
      (node (ref "U38") (pin "4") (pinfunction "C_4") (pintype "passive"))
    )
    (net (code "83") (name "Net-(U39-An)") (class "Default")
      (node (ref "R136") (pin "2") (pinfunction "2_2") (pintype "passive"))
      (node (ref "U39") (pin "1") (pinfunction "An_1") (pintype "passive"))
    )
    (net (code "84") (name "Net-(U39-C)") (class "Default")
      (node (ref "R132") (pin "1") (pinfunction "1_1") (pintype "passive"))
      (node (ref "R137") (pin "1") (pinfunction "1_1") (pintype "passive"))
      (node (ref "U39") (pin "4") (pinfunction "C_4") (pintype "passive"))
    )
    (net (code "85") (name "Net-(U40-An)") (class "Default")
      (node (ref "R138") (pin "2") (pinfunction "2_2") (pintype "passive"))
      (node (ref "U40") (pin "1") (pinfunction "An_1") (pintype "passive"))
    )
    (net (code "86") (name "Net-(U40-C)") (class "Default")
      (node (ref "R133") (pin "1") (pinfunction "1_1") (pintype "passive"))
      (node (ref "R139") (pin "1") (pinfunction "1_1") (pintype "passive"))
      (node (ref "U40") (pin "4") (pinfunction "C_4") (pintype "passive"))
    )
    (net (code "87") (name "Net-(U41-An)") (class "Default")
      (node (ref "R143") (pin "2") (pinfunction "2_2") (pintype "passive"))
      (node (ref "U41") (pin "1") (pinfunction "An_1") (pintype "passive"))
    )
    (net (code "88") (name "Net-(U41-C)") (class "Default")
      (node (ref "R140") (pin "1") (pinfunction "1_1") (pintype "passive"))
      (node (ref "R144") (pin "1") (pinfunction "1_1") (pintype "passive"))
      (node (ref "U41") (pin "4") (pinfunction "C_4") (pintype "passive"))
    )
    (net (code "89") (name "Net-(U42-An)") (class "Default")
      (node (ref "R145") (pin "2") (pinfunction "2_2") (pintype "passive"))
      (node (ref "U42") (pin "1") (pinfunction "An_1") (pintype "passive"))
    )
    (net (code "90") (name "Net-(U42-C)") (class "Default")
      (node (ref "R141") (pin "1") (pinfunction "1_1") (pintype "passive"))
      (node (ref "R146") (pin "1") (pinfunction "1_1") (pintype "passive"))
      (node (ref "U42") (pin "4") (pinfunction "C_4") (pintype "passive"))
    )
    (net (code "91") (name "Net-(U43-An)") (class "Default")
      (node (ref "R147") (pin "2") (pinfunction "2_2") (pintype "passive"))
      (node (ref "U43") (pin "1") (pinfunction "An_1") (pintype "passive"))
    )
    (net (code "92") (name "Net-(U43-C)") (class "Default")
      (node (ref "R142") (pin "1") (pinfunction "1_1") (pintype "passive"))
      (node (ref "R148") (pin "1") (pinfunction "1_1") (pintype "passive"))
      (node (ref "U43") (pin "4") (pinfunction "C_4") (pintype "passive"))
    )
    (net (code "93") (name "Net-(U44-An)") (class "Default")
      (node (ref "R152") (pin "2") (pinfunction "2_2") (pintype "passive"))
      (node (ref "U44") (pin "1") (pinfunction "An_1") (pintype "passive"))
    )
    (net (code "94") (name "Net-(U44-C)") (class "Default")
      (node (ref "R149") (pin "1") (pinfunction "1_1") (pintype "passive"))
      (node (ref "R153") (pin "1") (pinfunction "1_1") (pintype "passive"))
      (node (ref "U44") (pin "4") (pinfunction "C_4") (pintype "passive"))
    )
    (net (code "95") (name "Net-(U45-An)") (class "Default")
      (node (ref "R154") (pin "2") (pinfunction "2_2") (pintype "passive"))
      (node (ref "U45") (pin "1") (pinfunction "An_1") (pintype "passive"))
    )
    (net (code "96") (name "Net-(U45-C)") (class "Default")
      (node (ref "R150") (pin "1") (pinfunction "1_1") (pintype "passive"))
      (node (ref "R155") (pin "1") (pinfunction "1_1") (pintype "passive"))
      (node (ref "U45") (pin "4") (pinfunction "C_4") (pintype "passive"))
    )
    (net (code "97") (name "Net-(U46-An)") (class "Default")
      (node (ref "R156") (pin "2") (pinfunction "2_2") (pintype "passive"))
      (node (ref "U46") (pin "1") (pinfunction "An_1") (pintype "passive"))
    )
    (net (code "98") (name "Net-(U46-C)") (class "Default")
      (node (ref "R151") (pin "1") (pinfunction "1_1") (pintype "passive"))
      (node (ref "R157") (pin "1") (pinfunction "1_1") (pintype "passive"))
      (node (ref "U46") (pin "4") (pinfunction "C_4") (pintype "passive"))
    )
    (net (code "99") (name "Net-(U47-An)") (class "Default")
      (node (ref "R161") (pin "2") (pinfunction "2_2") (pintype "passive"))
      (node (ref "U47") (pin "1") (pinfunction "An_1") (pintype "passive"))
    )
    (net (code "100") (name "Net-(U47-C)") (class "Default")
      (node (ref "R158") (pin "1") (pinfunction "1_1") (pintype "passive"))
      (node (ref "R162") (pin "1") (pinfunction "1_1") (pintype "passive"))
      (node (ref "U47") (pin "4") (pinfunction "C_4") (pintype "passive"))
    )
    (net (code "101") (name "Net-(U48-An)") (class "Default")
      (node (ref "R163") (pin "2") (pinfunction "2_2") (pintype "passive"))
      (node (ref "U48") (pin "1") (pinfunction "An_1") (pintype "passive"))
    )
    (net (code "102") (name "Net-(U48-C)") (class "Default")
      (node (ref "R159") (pin "1") (pinfunction "1_1") (pintype "passive"))
      (node (ref "R164") (pin "1") (pinfunction "1_1") (pintype "passive"))
      (node (ref "U48") (pin "4") (pinfunction "C_4") (pintype "passive"))
    )
    (net (code "103") (name "Net-(U49-An)") (class "Default")
      (node (ref "R165") (pin "2") (pinfunction "2_2") (pintype "passive"))
      (node (ref "U49") (pin "1") (pinfunction "An_1") (pintype "passive"))
    )
    (net (code "104") (name "Net-(U49-C)") (class "Default")
      (node (ref "R160") (pin "1") (pinfunction "1_1") (pintype "passive"))
      (node (ref "R166") (pin "1") (pinfunction "1_1") (pintype "passive"))
      (node (ref "U49") (pin "4") (pinfunction "C_4") (pintype "passive"))
    )
  )
)
